# 13_iMX_8X_SYSTEM.net
KiCad netlist of a schematic drawn in Altium Designer
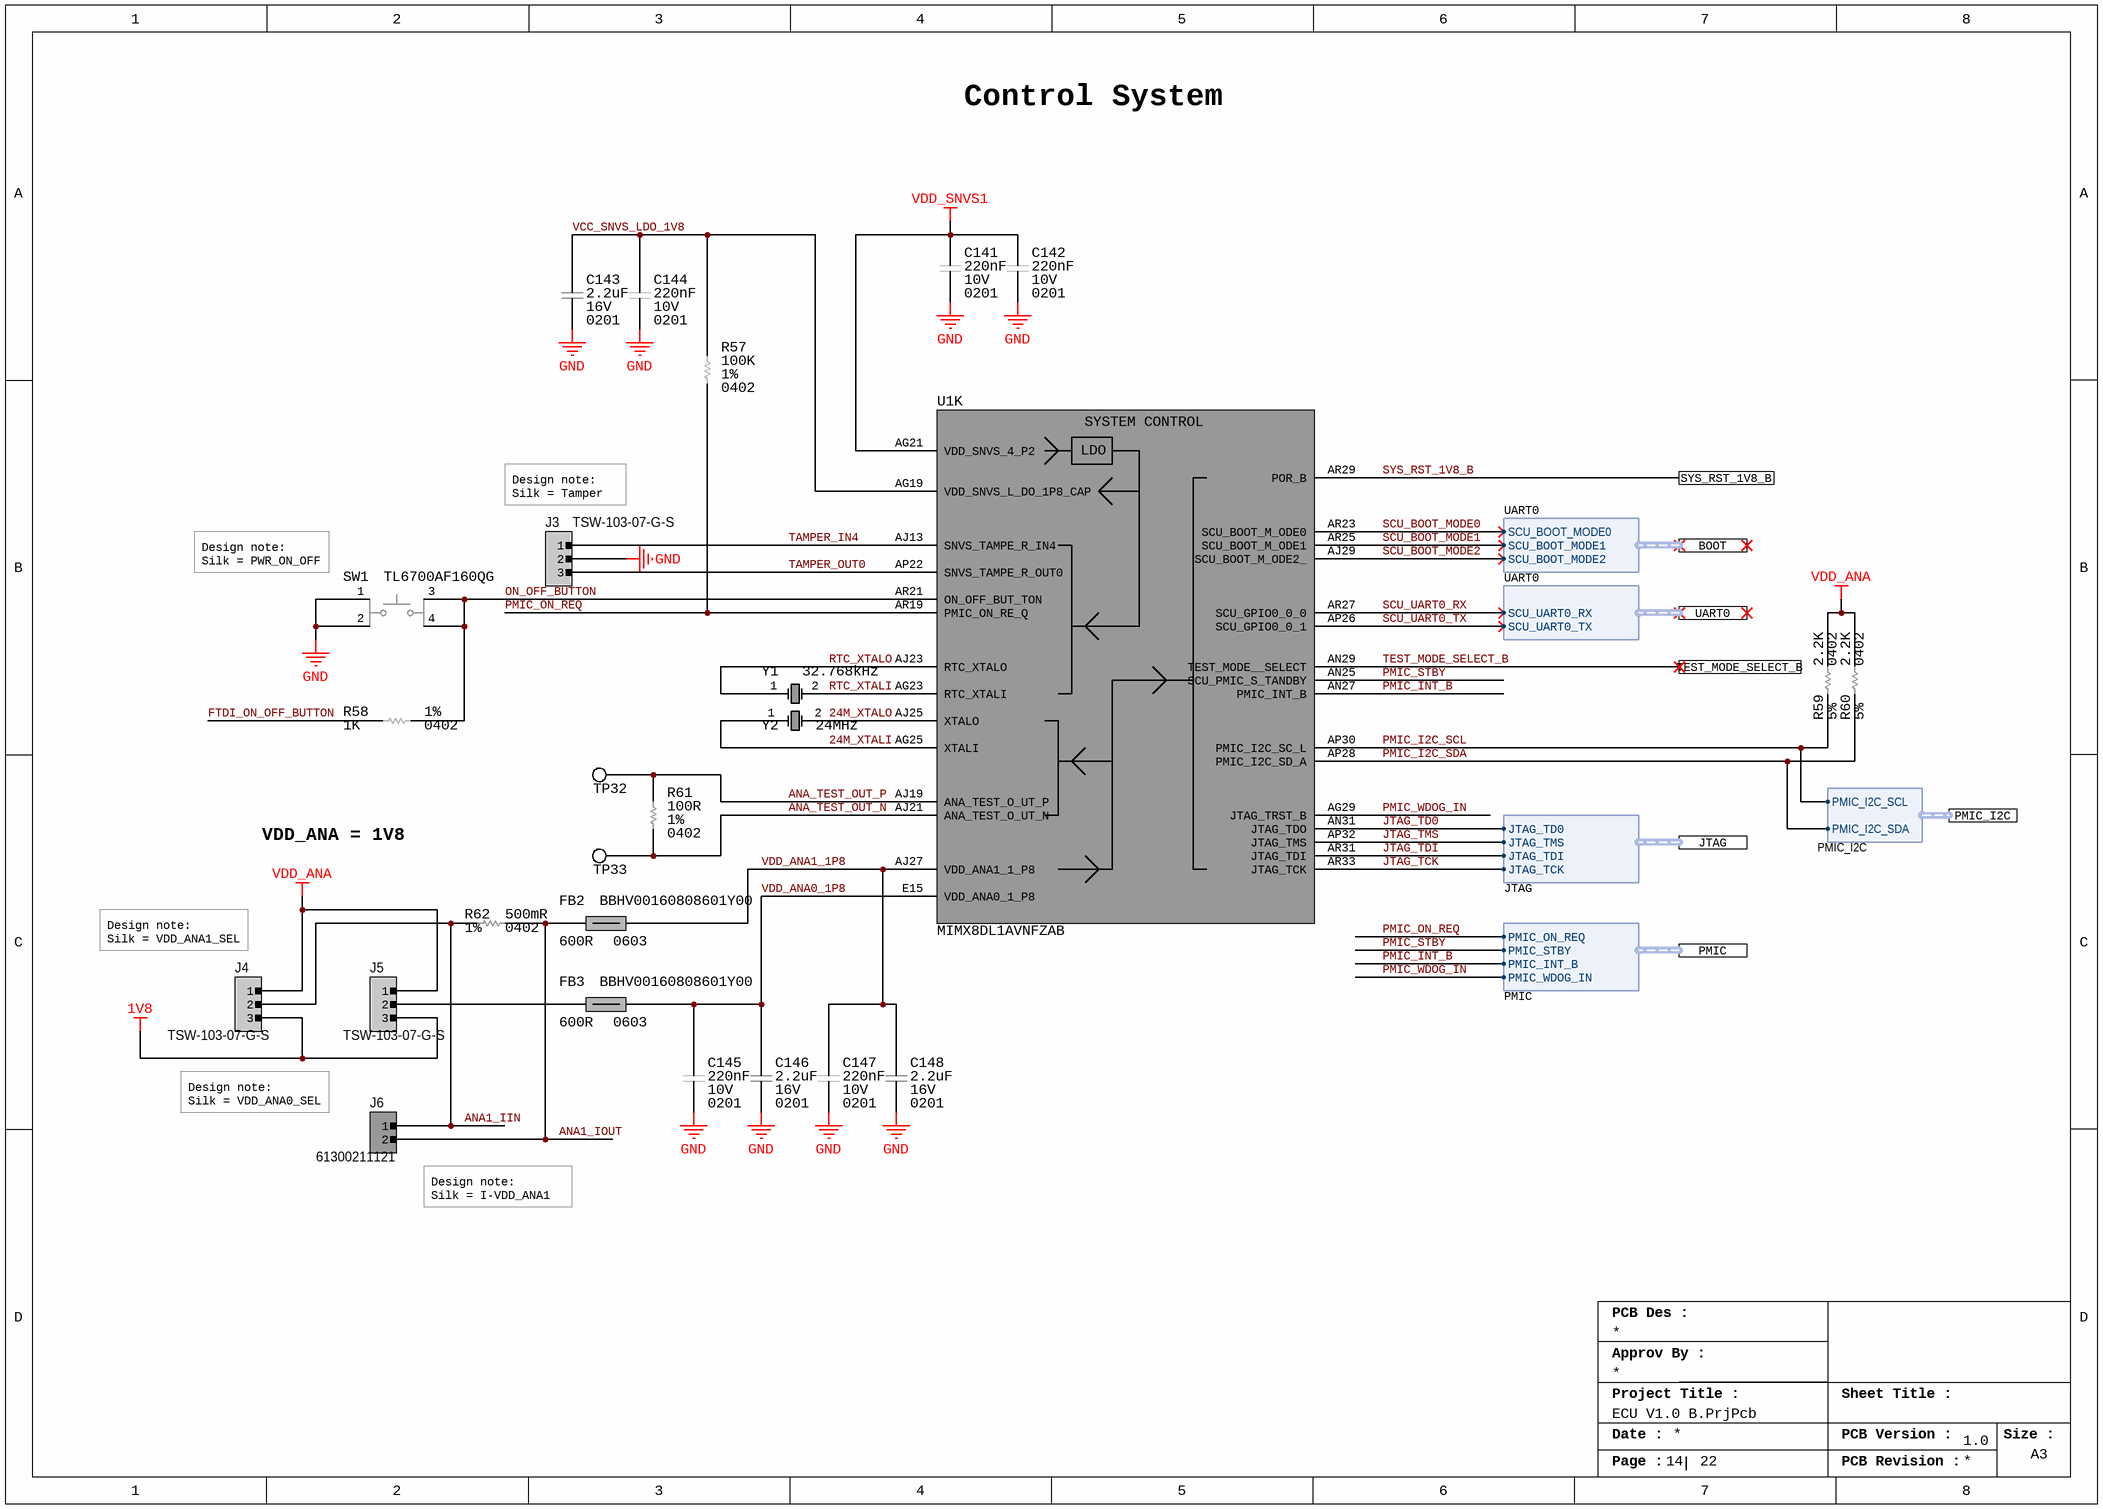
[diagram p0: 13_iMX 8X_SYSTEM.SchDoc]

(export (version "E")
  (design (tool "Eeschema 10.0.6"))
  (components
    (comp (ref "C141")
      (value "LMK063BJ224MP-F")
      (footprint "CAP_0201_CAPC0603X03N")
      (description "Multilayer Ceramic Capacitors (High dielectric type), 10V, 0.22 uF, ± 20 %, 0201, X5R, RoHS")
      (fields
        (field (name "MANUFACTURER") "Taiyo Yuden")
        (field (name "TOLERANCE") "20%")
        (field (name "VOLTAGE RATING (DC)") "10V")
        (field (name "CAPACITANCE") "220nF")
        (field (name "CASE/PACKAGE") "0201")
      )
      (libsource (lib "Electronic Devices_LIB") (part "CAP_0.22UF_10V_X5R_0201"))
    )
    (comp (ref "C142")
      (value "LMK063BJ224MP-F")
      (footprint "CAP_0201_CAPC0603X03N")
      (description "Multilayer Ceramic Capacitors (High dielectric type), 10V, 0.22 uF, ± 20 %, 0201, X5R, RoHS")
      (fields
        (field (name "MANUFACTURER") "Taiyo Yuden")
        (field (name "TOLERANCE") "20%")
        (field (name "VOLTAGE RATING (DC)") "10V")
        (field (name "CAPACITANCE") "220nF")
        (field (name "CASE/PACKAGE") "0201")
      )
      (libsource (lib "Electronic Devices_LIB") (part "CAP_0.22UF_10V_X5R_0201"))
    )
    (comp (ref "C143")
      (value "GRM035R61C225ME01D")
      (footprint "CAP_0201_CAPC0603X03N")
      (description "General Up to 85C Reflow soldering")
      (fields
        (field (name "MANUFACTURER") "Murata")
        (field (name "TOLERANCE") "20%")
        (field (name "CAPACITANCE") "2.2uF")
        (field (name "VOLTAGE RATING") "16V")
        (field (name "CASE/PACKAGE") "0201")
      )
      (libsource (lib "Electronic Devices_LIB") (part "CAP_2.2uF_16V_X5R_0201"))
    )
    (comp (ref "C144")
      (value "LMK063BJ224MP-F")
      (footprint "CAP_0201_CAPC0603X03N")
      (description "Multilayer Ceramic Capacitors (High dielectric type), 10V, 0.22 uF, ± 20 %, 0201, X5R, RoHS")
      (fields
        (field (name "MANUFACTURER") "Taiyo Yuden")
        (field (name "TOLERANCE") "20%")
        (field (name "VOLTAGE RATING (DC)") "10V")
        (field (name "CAPACITANCE") "220nF")
        (field (name "CASE/PACKAGE") "0201")
      )
      (libsource (lib "Electronic Devices_LIB") (part "CAP_0.22UF_10V_X5R_0201"))
    )
    (comp (ref "C145")
      (value "LMK063BJ224MP-F")
      (footprint "CAP_0201_CAPC0603X03N")
      (description "Multilayer Ceramic Capacitors (High dielectric type), 10V, 0.22 uF, ± 20 %, 0201, X5R, RoHS")
      (fields
        (field (name "MANUFACTURER") "Taiyo Yuden")
        (field (name "TOLERANCE") "20%")
        (field (name "VOLTAGE RATING (DC)") "10V")
        (field (name "CAPACITANCE") "220nF")
        (field (name "CASE/PACKAGE") "0201")
      )
      (libsource (lib "Electronic Devices_LIB") (part "CAP_0.22UF_10V_X5R_0201"))
    )
    (comp (ref "C146")
      (value "GRM035R61C225ME01D")
      (footprint "CAP_0201_CAPC0603X03N")
      (description "General Up to 85C Reflow soldering")
      (fields
        (field (name "MANUFACTURER") "Murata")
        (field (name "TOLERANCE") "20%")
        (field (name "CAPACITANCE") "2.2uF")
        (field (name "VOLTAGE RATING") "16V")
        (field (name "CASE/PACKAGE") "0201")
      )
      (libsource (lib "Electronic Devices_LIB") (part "CAP_2.2uF_16V_X5R_0201"))
    )
    (comp (ref "C147")
      (value "LMK063BJ224MP-F")
      (footprint "CAP_0201_CAPC0603X03N")
      (description "Multilayer Ceramic Capacitors (High dielectric type), 10V, 0.22 uF, ± 20 %, 0201, X5R, RoHS")
      (fields
        (field (name "MANUFACTURER") "Taiyo Yuden")
        (field (name "TOLERANCE") "20%")
        (field (name "VOLTAGE RATING (DC)") "10V")
        (field (name "CAPACITANCE") "220nF")
        (field (name "CASE/PACKAGE") "0201")
      )
      (libsource (lib "Electronic Devices_LIB") (part "CAP_0.22UF_10V_X5R_0201"))
    )
    (comp (ref "C148")
      (value "GRM035R61C225ME01D")
      (footprint "CAP_0201_CAPC0603X03N")
      (description "General Up to 85C Reflow soldering")
      (fields
        (field (name "MANUFACTURER") "Murata")
        (field (name "TOLERANCE") "20%")
        (field (name "CAPACITANCE") "2.2uF")
        (field (name "VOLTAGE RATING") "16V")
        (field (name "CASE/PACKAGE") "0201")
      )
      (libsource (lib "Electronic Devices_LIB") (part "CAP_2.2uF_16V_X5R_0201"))
    )
    (comp (ref "FB2")
      (value "BBHV00160808601Y00")
      (footprint "IND_0603_INDC1608X08N")
      (description "Ferrite Chip Bead 600Ohm 2A 0.1Ohm Multilayer 2-Pin 0603 T/R")
      (fields
        (field (name "MANUFACTURER") "Pulse")
        (field (name "IMPEDANCE") "600R")
        (field (name "CASE") "0603")
      )
      (libsource (lib "Electronic Devices_LIB") (part "IND_FERRITE_BEADS_600R_2A_BBHV00160808601Y00"))
    )
    (comp (ref "FB3")
      (value "BBHV00160808601Y00")
      (footprint "IND_0603_INDC1608X08N")
      (description "Ferrite Chip Bead 600Ohm 2A 0.1Ohm Multilayer 2-Pin 0603 T/R")
      (fields
        (field (name "MANUFACTURER") "Pulse")
        (field (name "IMPEDANCE") "600R")
        (field (name "CASE") "0603")
      )
      (libsource (lib "Electronic Devices_LIB") (part "IND_FERRITE_BEADS_600R_2A_BBHV00160808601Y00"))
    )
    (comp (ref "J3")
      (value "TSW-103-07-G-S")
      (footprint "CONN_HEADER_MALE_SAMTEC_TSW-103-07-G-S")
      (description "Conn Unshrouded Header HDR 3 POS 2.54mm Solder ST Top Entry Thru-Hole Bulk")
      (fields (field (name "MANUFACTURER") "Samtec"))
      (libsource (lib "Electronic Devices_LIB") (part "CONN_HEADER_MALE_3P_2.54mm_TSW-103-07-G-S"))
    )
    (comp (ref "J4")
      (value "TSW-103-07-G-S")
      (footprint "CONN_HEADER_MALE_SAMTEC_TSW-103-07-G-S")
      (description "Conn Unshrouded Header HDR 3 POS 2.54mm Solder ST Top Entry Thru-Hole Bulk")
      (fields (field (name "MANUFACTURER") "Samtec"))
      (libsource (lib "Electronic Devices_LIB") (part "CONN_HEADER_MALE_3P_2.54mm_TSW-103-07-G-S"))
    )
    (comp (ref "J5")
      (value "TSW-103-07-G-S")
      (footprint "CONN_HEADER_MALE_SAMTEC_TSW-103-07-G-S")
      (description "Conn Unshrouded Header HDR 3 POS 2.54mm Solder ST Top Entry Thru-Hole Bulk")
      (fields (field (name "MANUFACTURER") "Samtec"))
      (libsource (lib "Electronic Devices_LIB") (part "CONN_HEADER_MALE_3P_2.54mm_TSW-103-07-G-S"))
    )
    (comp (ref "J6")
      (value "61300211121")
      (footprint "HEADER_MALE_HDRV2W110P0X254_1X2_508X254X854P")
      (description "THT Vertical Pin Header WR-PHD, Pitch 2.54 mm, Single Row, 2 pins")
      (fields (field (name "MANUFACTURER") "Wurth Electronics"))
      (libsource (lib "Electronic Devices_LIB") (part "CONN_HEADER_MALE_2P_2.54_61300211121"))
    )
    (comp (ref "R57")
      (value "RC0402FR-07100KL")
      (footprint "RES_0402_RESC1005X04N")
      (description "SMD Chip Resistor, 100 kOhm, ± 1%, 63 mW, 0402 [1005 Metric], Thick Film, General Purpose")
      (fields
        (field (name "MANUFACTURER") "Yageo")
        (field (name "RESISTANCE") "100K")
        (field (name "TOLERANCE") "1%")
        (field (name "CASE/PACKAGE") "0402")
      )
      (libsource (lib "Electronic Devices_LIB") (part "RES_100K_1%_100mW_0402"))
    )
    (comp (ref "R58")
      (value "ERJ-2RKF1001X")
      (footprint "RES_0402_RESC1005X04N")
      (description "RES SMD 1K OHM 1% 1/10W 0402")
      (fields
        (field (name "MANUFACTURER") "Panasonic")
        (field (name "RESISTANCE") "1K")
        (field (name "TOLERANCE") "1%")
        (field (name "CASE/PACKAGE") "0402")
      )
      (libsource (lib "Electronic Devices_LIB") (part "RES_1K_1%_100mW_0402"))
    )
    (comp (ref "R59")
      (value "RC0402JR-072K2L")
      (footprint "RES_0402_RESC1005X04N")
      (description "SMD Chip Resistor, 2.2 kOhm, ± 5%, 63 mW, 0402 [1005 Metric], Thick Film, General Purpose")
      (fields
        (field (name "MANUFACTURER") "Yageo")
        (field (name "TOLERANCE") "5%")
        (field (name "RESISTANCE") "2.2K")
        (field (name "CASE/PACKAGE") "0402")
      )
      (libsource (lib "Electronic Devices_LIB") (part "RES_2.2K_5%_63mW_0402"))
    )
    (comp (ref "R60")
      (value "RC0402JR-072K2L")
      (footprint "RES_0402_RESC1005X04N")
      (description "SMD Chip Resistor, 2.2 kOhm, ± 5%, 63 mW, 0402 [1005 Metric], Thick Film, General Purpose")
      (fields
        (field (name "MANUFACTURER") "Yageo")
        (field (name "TOLERANCE") "5%")
        (field (name "RESISTANCE") "2.2K")
        (field (name "CASE/PACKAGE") "0402")
      )
      (libsource (lib "Electronic Devices_LIB") (part "RES_2.2K_5%_63mW_0402"))
    )
    (comp (ref "R61")
      (value "ERJ-2RKF1000X")
      (footprint "RES_0402_RESC1005X04N")
      (description "Resistor Thick Film 0402 100 Ohm 1% 1/10W 100ppm/C Molded SMD Punched Carrier T/R")
      (fields
        (field (name "MANUFACTURER") "Panasonic")
        (field (name "TOLERANCE") "1%")
        (field (name "RESISTANCE") "100R")
        (field (name "CASE/PACKAGE") "0402")
      )
      (libsource (lib "Electronic Devices_LIB") (part "RES_100R_1%_100mW_0402"))
    )
    (comp (ref "R62")
      (value "RL0402FR-070R5L")
      (footprint "RES_0603_RESC1608X04N")
      (description "SMD Current Sense Resistor, 0.5 ohm, RL Series, 0402 [1005 Metric], 63 mW, ï¿½ 1%, Thick Film")
      (fields
        (field (name "MANUFACTURER") "Yageo")
        (field (name "CASE/PACKAGE") "0402")
        (field (name "TOLERANCE") "1%")
        (field (name "RESISTANCE") "500mR")
      )
      (libsource (lib "Electronic Devices_LIB") (part "RES_0.5R_63mW_0402"))
    )
    (comp (ref "SW1")
      (value "TL6700AF160QG")
      (footprint "SW_TL6700AF160QG")
      (description "TL6700 Series SPST 1.6 N Round Button Gull Wing SMT Sealed Tactile Switch")
      (fields (field (name "MANUFACTURER") "E-Switch"))
      (libsource (lib "Electronic Devices_LIB") (part "SWITCH_SPST_TL6700AF160QG"))
    )
    (comp (ref "TP32")
      (value "NO COMPONENT")
      (footprint "TP_PAD_0.5MM_SMD_ROUND")
      (description "Test Point, SMD pad, round, 1.5mm, 1.6mm, 3mm diameter")
      (libsource (lib "Electronic Devices_LIB") (part "TP_PAD_SMD_SMALL"))
    )
    (comp (ref "TP33")
      (value "NO COMPONENT")
      (footprint "TP_PAD_0.5MM_SMD_ROUND")
      (description "Test Point, SMD pad, round, 1.5mm, 1.6mm, 3mm diameter")
      (libsource (lib "Electronic Devices_LIB") (part "TP_PAD_SMD_SMALL"))
    )
    (comp (ref "U1")
      (value "MIMX8DL1AVNFZAB")
      (footprint "MIMX8DL1AVNFZAB")
      (description "I.MX8 Dxl 15SQ / Tray Rohs Compliant: Yes")
      (fields (field (name "MANUFACTURER") "NXP Semiconductors"))
      (libsource (lib "Electronic Devices_LIB") (part "IC_MPU_ARM_1.2GHz_MIMX8DL1AVNFZAB"))
    )
    (comp (ref "Y1")
      (value "FC-135 32.7680KA-AG5")
      (footprint "CRYSTAL_FC135327680KAAG5")
      (description "Crystal 0.032768MHz ±20ppm (Tol) 7pF FUND 70000Ohm 2-Pin SMD T/R")
      (fields (field (name "MANUFACTURER") "Epson") (field (name "FREQUENCY") "32.768kHz"))
      (libsource (lib "Electronic Devices_LIB") (part "CRYSTAL_EPSON_32.768KHZ"))
    )
    (comp (ref "Y2")
      (value "ECS-240-18-23A-EN-TR")
      (footprint "CRYSTAL_ECS-240-18-23A-EN-TR")
      (description "Crystal 24MHz ±30ppm (Tol) ±50ppm (Stability) 18pF FUND 30Ohm 2-Pin Mini-SMD T/R")
      (fields (field (name "MANUFACTURER") "ECS International") (field (name "FREQUENCY") "24MHz"))
      (libsource (lib "Electronic Devices_LIB") (part "CRYSTAL_ECS_24MHZ"))
    )
  )
  (nets
    (net (code "5") (name "/24M_XTALI") (class "Default")
      (node (ref "U1") (pin "AG25") (pinfunction "XTALI_AG25") (pintype "passive"))
      (node (ref "Y2") (pin "1") (pinfunction "OSC1_1") (pintype "passive"))
    )
    (net (code "6") (name "/24M_XTALO") (class "Default")
      (node (ref "U1") (pin "AJ25") (pinfunction "XTALO_AJ25") (pintype "passive"))
      (node (ref "Y2") (pin "2") (pinfunction "OSC2_2") (pintype "passive"))
    )
    (net (code "7") (name "/ANA1_IIN") (class "Default")
      (node (ref "J4") (pin "2") (pinfunction "2_2") (pintype "passive"))
      (node (ref "J6") (pin "1") (pinfunction "1_1") (pintype "passive"))
      (node (ref "R62") (pin "1") (pinfunction "1_1") (pintype "passive"))
    )
    (net (code "8") (name "/ANA1_IOUT") (class "Default")
      (node (ref "FB2") (pin "1") (pinfunction "1_1") (pintype "passive"))
      (node (ref "J6") (pin "2") (pinfunction "2_2") (pintype "passive"))
      (node (ref "R62") (pin "2") (pinfunction "2_2") (pintype "passive"))
    )
    (net (code "9") (name "/ANA_TEST_OUT_N") (class "Default")
      (node (ref "R61") (pin "1") (pinfunction "1_1") (pintype "passive"))
      (node (ref "TP33") (pin "1") (pinfunction "1_1") (pintype "passive"))
      (node (ref "U1") (pin "AJ21") (pinfunction "ANA_TEST_O_UT_N_AJ21") (pintype "passive"))
    )
    (net (code "10") (name "/ANA_TEST_OUT_P") (class "Default")
      (node (ref "R61") (pin "2") (pinfunction "2_2") (pintype "passive"))
      (node (ref "TP32") (pin "1") (pinfunction "1_1") (pintype "passive"))
      (node (ref "U1") (pin "AJ19") (pinfunction "ANA_TEST_O_UT_P_AJ19") (pintype "passive"))
    )
    (net (code "11") (name "/FTDI_ON_OFF_BUTTON") (class "Default")
      (node (ref "R58") (pin "1") (pinfunction "1_1") (pintype "passive"))
    )
    (net (code "12") (name "/JTAG_TCK") (class "Default")
      (node (ref "U1") (pin "AR33") (pinfunction "JTAG_TCK_AR33") (pintype "passive"))
    )
    (net (code "13") (name "/JTAG_TD0") (class "Default")
      (node (ref "U1") (pin "AN31") (pinfunction "JTAG_TDO_AN31") (pintype "passive"))
    )
    (net (code "14") (name "/JTAG_TDI") (class "Default")
      (node (ref "U1") (pin "AR31") (pinfunction "JTAG_TDI_AR31") (pintype "passive"))
    )
    (net (code "15") (name "/JTAG_TMS") (class "Default")
      (node (ref "U1") (pin "AP32") (pinfunction "JTAG_TMS_AP32") (pintype "passive"))
    )
    (net (code "16") (name "/ON_OFF_BUTTON") (class "Default")
      (node (ref "R58") (pin "2") (pinfunction "2_2") (pintype "passive"))
      (node (ref "SW1") (pin "3") (pinfunction "3_3") (pintype "passive"))
      (node (ref "SW1") (pin "4") (pinfunction "4_4") (pintype "passive"))
      (node (ref "U1") (pin "AR21") (pinfunction "ON_OFF_BUT_TON_AR21") (pintype "passive"))
    )
    (net (code "17") (name "/PMIC_I2C_SCL") (class "Default")
      (node (ref "R59") (pin "1") (pinfunction "1_1") (pintype "passive"))
      (node (ref "U1") (pin "AP30") (pinfunction "PMIC_I2C_SC_L_AP30") (pintype "passive"))
    )
    (net (code "18") (name "/PMIC_I2C_SDA") (class "Default")
      (node (ref "R60") (pin "1") (pinfunction "1_1") (pintype "passive"))
      (node (ref "U1") (pin "AP28") (pinfunction "PMIC_I2C_SD_A_AP28") (pintype "passive"))
    )
    (net (code "19") (name "/PMIC_INT_B") (class "Default")
      (node (ref "U1") (pin "AN27") (pinfunction "PMIC_INT_B_AN27") (pintype "passive"))
    )
    (net (code "20") (name "/PMIC_ON_REQ") (class "Default")
      (node (ref "R57") (pin "1") (pinfunction "1_1") (pintype "passive"))
      (node (ref "U1") (pin "AR19") (pinfunction "PMIC_ON_RE_Q_AR19") (pintype "passive"))
    )
    (net (code "21") (name "/PMIC_STBY") (class "Default")
      (node (ref "U1") (pin "AN25") (pinfunction "SCU_PMIC_S_TANDBY_AN25") (pintype "passive"))
    )
    (net (code "22") (name "/PMIC_WDOG_IN") (class "Default")
      (node (ref "U1") (pin "AG29") (pinfunction "JTAG_TRST_B_AG29") (pintype "passive"))
    )
    (net (code "23") (name "/RTC_XTALI") (class "Default")
      (node (ref "U1") (pin "AG23") (pinfunction "RTC_XTALI_AG23") (pintype "passive"))
      (node (ref "Y1") (pin "2") (pinfunction "OSC2_2") (pintype "passive"))
    )
    (net (code "24") (name "/RTC_XTALO") (class "Default")
      (node (ref "U1") (pin "AJ23") (pinfunction "RTC_XTALO_AJ23") (pintype "passive"))
      (node (ref "Y1") (pin "1") (pinfunction "OSC1_1") (pintype "passive"))
    )
    (net (code "25") (name "/SCU_BOOT_MODE0") (class "Default")
      (node (ref "U1") (pin "AR23") (pinfunction "SCU_BOOT_M_ODE0_AR23") (pintype "passive+no_connect"))
    )
    (net (code "26") (name "/SCU_BOOT_MODE1") (class "Default")
      (node (ref "U1") (pin "AR25") (pinfunction "SCU_BOOT_M_ODE1_AR25") (pintype "passive+no_connect"))
    )
    (net (code "27") (name "/SCU_BOOT_MODE2") (class "Default")
      (node (ref "U1") (pin "AJ29") (pinfunction "SCU_BOOT_M_ODE2__AJ29") (pintype "passive+no_connect"))
    )
    (net (code "28") (name "/SCU_UART0_RX") (class "Default")
      (node (ref "U1") (pin "AR27") (pinfunction "SCU_GPIO0_0_0_AR27") (pintype "passive+no_connect"))
    )
    (net (code "29") (name "/SCU_UART0_TX") (class "Default")
      (node (ref "U1") (pin "AP26") (pinfunction "SCU_GPIO0_0_1_AP26") (pintype "passive+no_connect"))
    )
    (net (code "30") (name "/SYS_RST_1V8_B") (class "Default")
      (node (ref "U1") (pin "AR29") (pinfunction "POR_B_AR29") (pintype "passive"))
    )
    (net (code "31") (name "/TAMPER_IN4") (class "Default")
      (node (ref "J3") (pin "1") (pinfunction "1_1") (pintype "passive"))
      (node (ref "U1") (pin "AJ13") (pinfunction "SNVS_TAMPE_R_IN4_AJ13") (pintype "passive"))
    )
    (net (code "32") (name "/TAMPER_OUT0") (class "Default")
      (node (ref "J3") (pin "3") (pinfunction "3_3") (pintype "passive"))
      (node (ref "U1") (pin "AP22") (pinfunction "SNVS_TAMPE_R_OUT0_AP22") (pintype "passive"))
    )
    (net (code "33") (name "/TEST_MODE_SELECT_B") (class "Default")
      (node (ref "U1") (pin "AN29") (pinfunction "TEST_MODE__SELECT_AN29") (pintype "passive+no_connect"))
    )
    (net (code "34") (name "/VCC_SNVS_LDO_1V8") (class "Default")
      (node (ref "C143") (pin "2") (pinfunction "2_2") (pintype "passive"))
      (node (ref "C144") (pin "2") (pinfunction "2_2") (pintype "passive"))
      (node (ref "R57") (pin "2") (pinfunction "2_2") (pintype "passive"))
      (node (ref "U1") (pin "AG19") (pinfunction "VDD_SNVS_L_DO_1P8_CAP_AG19") (pintype "passive"))
    )
    (net (code "35") (name "/VDD_ANA0_1P8") (class "Default")
      (node (ref "C145") (pin "2") (pinfunction "2_2") (pintype "passive"))
      (node (ref "C146") (pin "2") (pinfunction "2_2") (pintype "passive"))
      (node (ref "FB3") (pin "2") (pinfunction "2_2") (pintype "passive"))
      (node (ref "U1") (pin "E15") (pinfunction "VDD_ANA0_1_P8_E15") (pintype "passive"))
    )
    (net (code "36") (name "/VDD_ANA1_1P8") (class "Default")
      (node (ref "C147") (pin "2") (pinfunction "2_2") (pintype "passive"))
      (node (ref "C148") (pin "2") (pinfunction "2_2") (pintype "passive"))
      (node (ref "FB2") (pin "2") (pinfunction "2_2") (pintype "passive"))
      (node (ref "U1") (pin "AJ27") (pinfunction "VDD_ANA1_1_P8_AJ27") (pintype "passive"))
    )
    (net (code "41") (name "1V8") (class "Default")
      (node (ref "J4") (pin "3") (pinfunction "3_3") (pintype "passive"))
      (node (ref "J5") (pin "3") (pinfunction "3_3") (pintype "passive"))
    )
    (net (code "42") (name "GND") (class "Default")
      (node (ref "C141") (pin "1") (pinfunction "1_1") (pintype "passive"))
      (node (ref "C142") (pin "1") (pinfunction "1_1") (pintype "passive"))
      (node (ref "C143") (pin "1") (pinfunction "1_1") (pintype "passive"))
      (node (ref "C144") (pin "1") (pinfunction "1_1") (pintype "passive"))
      (node (ref "C145") (pin "1") (pinfunction "1_1") (pintype "passive"))
      (node (ref "C146") (pin "1") (pinfunction "1_1") (pintype "passive"))
      (node (ref "C147") (pin "1") (pinfunction "1_1") (pintype "passive"))
      (node (ref "C148") (pin "1") (pinfunction "1_1") (pintype "passive"))
      (node (ref "J3") (pin "2") (pinfunction "2_2") (pintype "passive"))
      (node (ref "SW1") (pin "1") (pinfunction "1_1") (pintype "passive"))
      (node (ref "SW1") (pin "2") (pinfunction "2_2") (pintype "passive"))
    )
    (net (code "43") (name "Net-(FB3-Pad1)") (class "Default")
      (node (ref "FB3") (pin "1") (pinfunction "1_1") (pintype "passive"))
      (node (ref "J5") (pin "2") (pinfunction "2_2") (pintype "passive"))
    )
    (net (code "44") (name "VDD_ANA") (class "Default")
      (node (ref "J4") (pin "1") (pinfunction "1_1") (pintype "passive"))
      (node (ref "J5") (pin "1") (pinfunction "1_1") (pintype "passive"))
      (node (ref "R59") (pin "2") (pinfunction "2_2") (pintype "passive"))
      (node (ref "R60") (pin "2") (pinfunction "2_2") (pintype "passive"))
    )
    (net (code "45") (name "VDD_SNVS1") (class "Default")
      (node (ref "C141") (pin "2") (pinfunction "2_2") (pintype "passive"))
      (node (ref "C142") (pin "2") (pinfunction "2_2") (pintype "passive"))
      (node (ref "U1") (pin "AG21") (pinfunction "VDD_SNVS_4_P2_AG21") (pintype "passive"))
    )
  )
)
